# AlarmClock.net
KiCad netlist of a schematic drawn in EAGLE
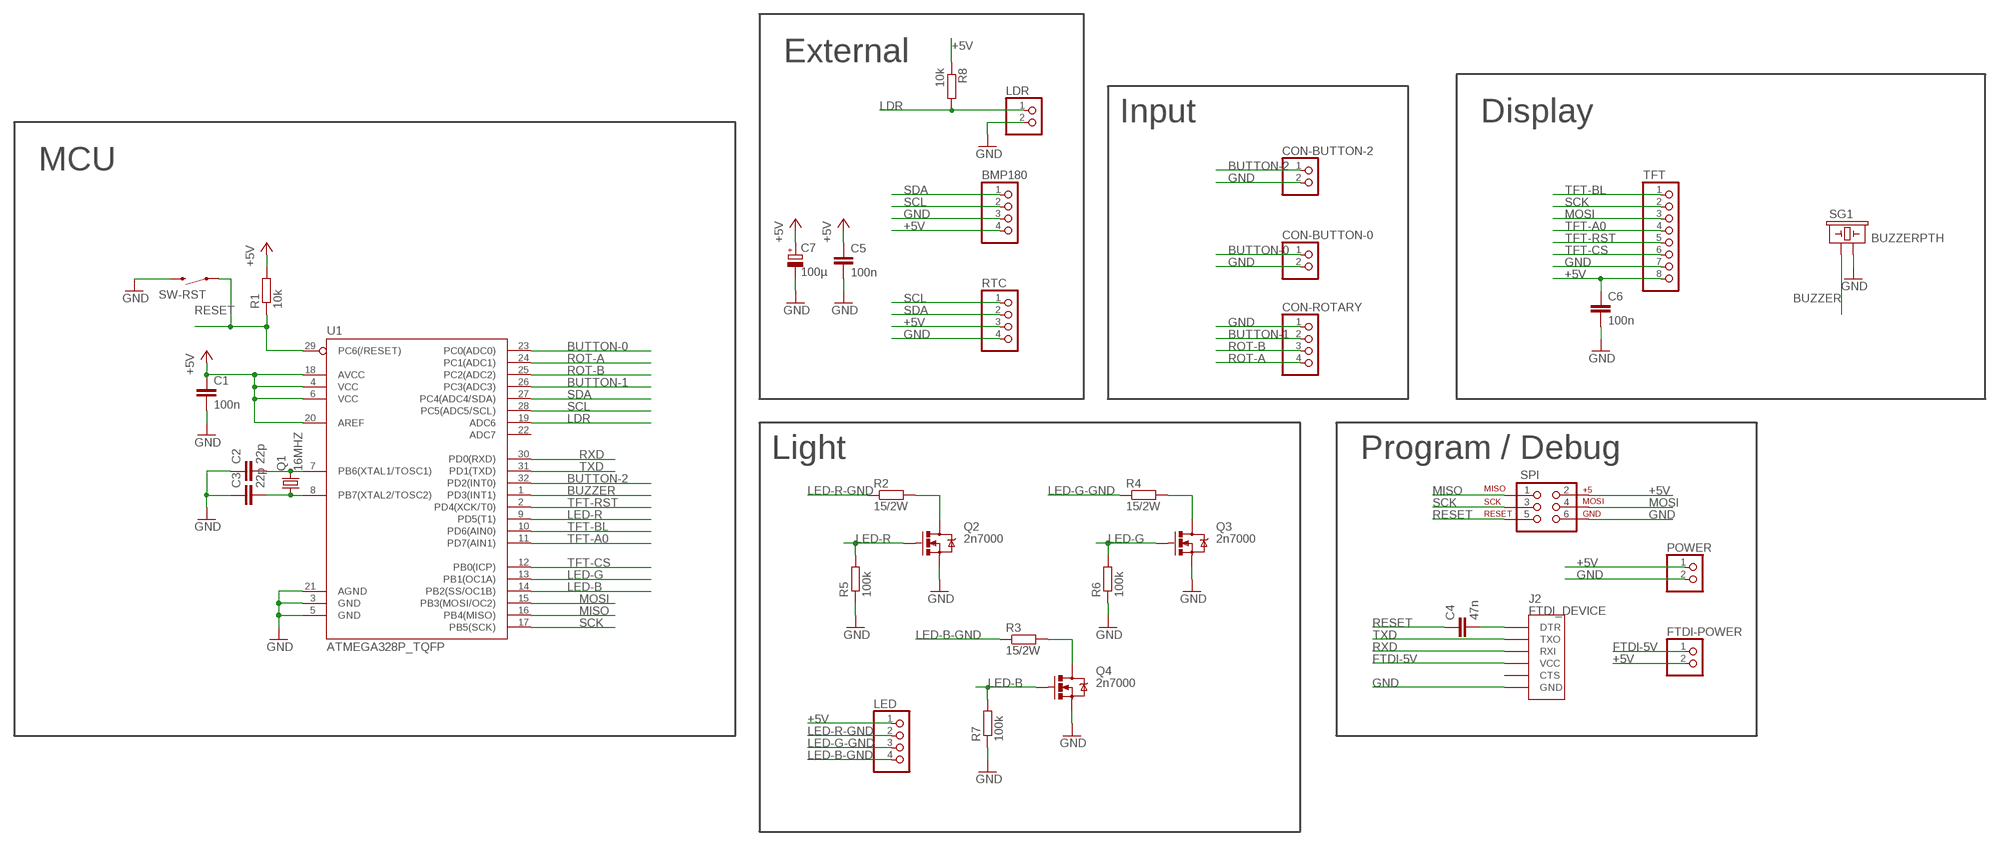
[diagram p0: schematic, sheet 1]

(export (version "E")
  (design (tool "Eeschema 10.0.6"))
  (components
    (comp (ref "BMP180")
      (value "PINHD-1X4")
      (footprint "eagle-import:1X04")
      (libsource (lib "eagle-import") (part "PINHD-1X4"))
    )
    (comp (ref "C1")
      (value "100n")
      (footprint "eagle-import:C0805")
      (libsource (lib "eagle-import") (part "C-EUC0805"))
    )
    (comp (ref "C2")
      (value "22p")
      (footprint "eagle-import:C0805")
      (libsource (lib "eagle-import") (part "C-EUC0805"))
    )
    (comp (ref "C3")
      (value "22p")
      (footprint "eagle-import:C0805")
      (libsource (lib "eagle-import") (part "C-EUC0805"))
    )
    (comp (ref "C4")
      (value "47n")
      (footprint "eagle-import:C0805")
      (libsource (lib "eagle-import") (part "C-EUC0805"))
    )
    (comp (ref "C5")
      (value "100n")
      (footprint "eagle-import:C0805")
      (libsource (lib "eagle-import") (part "C-EUC0805"))
    )
    (comp (ref "C6")
      (value "100n")
      (footprint "eagle-import:C0805")
      (libsource (lib "eagle-import") (part "C-EUC0805"))
    )
    (comp (ref "C7")
      (value "100µ")
      (footprint "eagle-import:PANASONIC_F")
      (libsource (lib "eagle-import") (part "CPOL-EUF"))
    )
    (comp (ref "CON-BUTTON-0")
      (value "PINHD-1X2/90")
      (footprint "eagle-import:1X02_90")
      (libsource (lib "eagle-import") (part "PINHD-1X2/90"))
    )
    (comp (ref "CON-BUTTON-2")
      (value "PINHD-1X2/90")
      (footprint "eagle-import:1X02_90")
      (libsource (lib "eagle-import") (part "PINHD-1X2/90"))
    )
    (comp (ref "CON-ROTARY")
      (value "PINHD-1X4/90")
      (footprint "eagle-import:1X04_90")
      (libsource (lib "eagle-import") (part "PINHD-1X4/90"))
    )
    (comp (ref "FTDI-POWER")
      (value "PINHD-1X2")
      (footprint "eagle-import:1X02")
      (libsource (lib "eagle-import") (part "PINHD-1X2"))
    )
    (comp (ref "J2")
      (value "FTDI_DEVICE")
      (footprint "eagle-import:FTDI_DEVICE_SIDE")
      (libsource (lib "eagle-import") (part "FTDI_DEVICE"))
    )
    (comp (ref "LDR")
      (value "PINHD-1X2")
      (footprint "eagle-import:1X02")
      (libsource (lib "eagle-import") (part "PINHD-1X2"))
    )
    (comp (ref "LED")
      (value "PINHD-1X4")
      (footprint "eagle-import:1X04")
      (libsource (lib "eagle-import") (part "PINHD-1X4"))
    )
    (comp (ref "POWER")
      (value "PINHD-1X2")
      (footprint "eagle-import:1X02")
      (libsource (lib "eagle-import") (part "PINHD-1X2"))
    )
    (comp (ref "Q1")
      (value "16MHZ")
      (footprint "eagle-import:HC49UP")
      (libsource (lib "eagle-import") (part "CRYSTALHC49UP"))
    )
    (comp (ref "Q2")
      (value "2n7000")
      (footprint "eagle-import:TO-92")
      (libsource (lib "eagle-import") (part "MOSFET-NCHANNEL2N7000"))
    )
    (comp (ref "Q3")
      (value "2n7000")
      (footprint "eagle-import:TO-92")
      (libsource (lib "eagle-import") (part "MOSFET-NCHANNEL2N7000"))
    )
    (comp (ref "Q4")
      (value "2n7000")
      (footprint "eagle-import:TO-92")
      (libsource (lib "eagle-import") (part "MOSFET-NCHANNEL2N7000"))
    )
    (comp (ref "R1")
      (value "10k")
      (footprint "eagle-import:M0805")
      (libsource (lib "eagle-import") (part "R-EU_M0805"))
    )
    (comp (ref "R2")
      (value "15/2W")
      (footprint "eagle-import:0414_15")
      (libsource (lib "eagle-import") (part "R-EU_0414/15"))
    )
    (comp (ref "R3")
      (value "15/2W")
      (footprint "eagle-import:0414_15")
      (libsource (lib "eagle-import") (part "R-EU_0414/15"))
    )
    (comp (ref "R4")
      (value "15/2W")
      (footprint "eagle-import:0414_15")
      (libsource (lib "eagle-import") (part "R-EU_0414/15"))
    )
    (comp (ref "R5")
      (value "100k")
      (footprint "eagle-import:M0805")
      (libsource (lib "eagle-import") (part "R-EU_M0805"))
    )
    (comp (ref "R6")
      (value "100k")
      (footprint "eagle-import:M0805")
      (libsource (lib "eagle-import") (part "R-EU_M0805"))
    )
    (comp (ref "R7")
      (value "100k")
      (footprint "eagle-import:M0805")
      (libsource (lib "eagle-import") (part "R-EU_M0805"))
    )
    (comp (ref "R8")
      (value "10k")
      (footprint "eagle-import:R0805")
      (libsource (lib "eagle-import") (part "R-EU_R0805"))
    )
    (comp (ref "RTC")
      (value "PINHD-1X4")
      (footprint "eagle-import:1X04")
      (libsource (lib "eagle-import") (part "PINHD-1X4"))
    )
    (comp (ref "SG1")
      (value "BUZZERPTH")
      (footprint "eagle-import:BUZZER-12MM")
      (libsource (lib "eagle-import") (part "BUZZERPTH"))
    )
    (comp (ref "SPI")
      (value "AVR_SPI_PRG_6NS")
      (footprint "eagle-import:2X3-NS")
      (libsource (lib "eagle-import") (part "AVR_SPI_PRG_6NS"))
    )
    (comp (ref "SW-RST")
      (value "SWITCH-MOMENTARY-2SMD-1101NE")
      (footprint "eagle-import:TACTILE-SWITCH-1101NE")
      (libsource (lib "eagle-import") (part "SWITCH-MOMENTARY-2SMD-1101NE"))
    )
    (comp (ref "TFT")
      (value "PINHD-1X8")
      (footprint "eagle-import:1X08")
      (libsource (lib "eagle-import") (part "PINHD-1X8"))
    )
    (comp (ref "U1")
      (value "ATMEGA328P_TQFP")
      (footprint "eagle-import:TQFP32-08")
      (libsource (lib "eagle-import") (part "ATMEGA328P_TQFP"))
    )
  )
  (nets
    (net (code "1") (name "+5V") (class "Default")
      (node (ref "BMP180") (pin "4") (pinfunction "4_4") (pintype "passive"))
      (node (ref "C1") (pin "1") (pinfunction "1_1") (pintype "passive"))
      (node (ref "C5") (pin "1") (pinfunction "1_1") (pintype "passive"))
      (node (ref "C6") (pin "1") (pinfunction "1_1") (pintype "passive"))
      (node (ref "C7") (pin "+") (pinfunction "+_+") (pintype "passive"))
      (node (ref "FTDI-POWER") (pin "2") (pinfunction "2_2") (pintype "passive"))
      (node (ref "LED") (pin "1") (pinfunction "1_1") (pintype "passive"))
      (node (ref "POWER") (pin "1") (pinfunction "1_1") (pintype "passive"))
      (node (ref "R1") (pin "2") (pinfunction "2_2") (pintype "passive"))
      (node (ref "R8") (pin "1") (pinfunction "1_1") (pintype "passive"))
      (node (ref "RTC") (pin "3") (pinfunction "3_3") (pintype "passive"))
      (node (ref "SPI") (pin "2") (pinfunction "2_2") (pintype "passive"))
      (node (ref "TFT") (pin "8") (pinfunction "8_8") (pintype "passive"))
      (node (ref "U1") (pin "18") (pinfunction "AVCC_18") (pintype "bidirectional"))
      (node (ref "U1") (pin "20") (pinfunction "AREF_20") (pintype "bidirectional"))
      (node (ref "U1") (pin "4") (pinfunction "VCC_4") (pintype "bidirectional"))
      (node (ref "U1") (pin "6") (pinfunction "VCC_6") (pintype "bidirectional"))
    )
    (net (code "2") (name "/BUTTON-0") (class "Default")
      (node (ref "CON-BUTTON-0") (pin "1") (pinfunction "1_1") (pintype "passive"))
      (node (ref "U1") (pin "23") (pinfunction "PC0(ADC0)_23") (pintype "bidirectional"))
    )
    (net (code "3") (name "/BUTTON-1") (class "Default")
      (node (ref "CON-ROTARY") (pin "2") (pinfunction "2_2") (pintype "passive"))
      (node (ref "U1") (pin "26") (pinfunction "PC3(ADC3)_26") (pintype "bidirectional"))
    )
    (net (code "4") (name "/BUTTON-2") (class "Default")
      (node (ref "CON-BUTTON-2") (pin "1") (pinfunction "1_1") (pintype "passive"))
      (node (ref "U1") (pin "32") (pinfunction "PD2(INT0)_32") (pintype "bidirectional"))
    )
    (net (code "5") (name "/BUZZER") (class "Default")
      (node (ref "SG1") (pin "+") (pinfunction "1_+") (pintype "passive"))
      (node (ref "U1") (pin "1") (pinfunction "PD3(INT1)_1") (pintype "bidirectional"))
    )
    (net (code "6") (name "/FTDI-5V") (class "Default")
      (node (ref "FTDI-POWER") (pin "1") (pinfunction "1_1") (pintype "passive"))
      (node (ref "J2") (pin "P$4") (pinfunction "VCC_P$4") (pintype "bidirectional"))
    )
    (net (code "7") (name "/LDR") (class "Default")
      (node (ref "LDR") (pin "1") (pinfunction "1_1") (pintype "passive"))
      (node (ref "R8") (pin "2") (pinfunction "2_2") (pintype "passive"))
      (node (ref "U1") (pin "19") (pinfunction "ADC6_19") (pintype "bidirectional"))
    )
    (net (code "8") (name "/LED-B") (class "Default")
      (node (ref "Q4") (pin "2") (pinfunction "G_2") (pintype "passive"))
      (node (ref "R7") (pin "2") (pinfunction "2_2") (pintype "passive"))
      (node (ref "U1") (pin "14") (pinfunction "PB2(SS/OC1B)_14") (pintype "bidirectional"))
    )
    (net (code "9") (name "/LED-B-GND") (class "Default")
      (node (ref "LED") (pin "4") (pinfunction "4_4") (pintype "passive"))
      (node (ref "R3") (pin "1") (pinfunction "1_1") (pintype "passive"))
    )
    (net (code "10") (name "/LED-G") (class "Default")
      (node (ref "Q3") (pin "2") (pinfunction "G_2") (pintype "passive"))
      (node (ref "R6") (pin "2") (pinfunction "2_2") (pintype "passive"))
      (node (ref "U1") (pin "13") (pinfunction "PB1(OC1A)_13") (pintype "bidirectional"))
    )
    (net (code "11") (name "/LED-G-GND") (class "Default")
      (node (ref "LED") (pin "3") (pinfunction "3_3") (pintype "passive"))
      (node (ref "R4") (pin "1") (pinfunction "1_1") (pintype "passive"))
    )
    (net (code "12") (name "/LED-R") (class "Default")
      (node (ref "Q2") (pin "2") (pinfunction "G_2") (pintype "passive"))
      (node (ref "R5") (pin "2") (pinfunction "2_2") (pintype "passive"))
      (node (ref "U1") (pin "9") (pinfunction "PD5(T1)_9") (pintype "bidirectional"))
    )
    (net (code "13") (name "/LED-R-GND") (class "Default")
      (node (ref "LED") (pin "2") (pinfunction "2_2") (pintype "passive"))
      (node (ref "R2") (pin "1") (pinfunction "1_1") (pintype "passive"))
    )
    (net (code "14") (name "/MISO") (class "Default")
      (node (ref "SPI") (pin "1") (pinfunction "1_1") (pintype "passive"))
      (node (ref "U1") (pin "16") (pinfunction "PB4(MISO)_16") (pintype "bidirectional"))
    )
    (net (code "15") (name "/MOSI") (class "Default")
      (node (ref "SPI") (pin "4") (pinfunction "4_4") (pintype "passive"))
      (node (ref "TFT") (pin "3") (pinfunction "3_3") (pintype "passive"))
      (node (ref "U1") (pin "15") (pinfunction "PB3(MOSI/OC2)_15") (pintype "bidirectional"))
    )
    (net (code "16") (name "/RESET") (class "Default")
      (node (ref "C4") (pin "1") (pinfunction "1_1") (pintype "passive"))
      (node (ref "R1") (pin "1") (pinfunction "1_1") (pintype "passive"))
      (node (ref "SPI") (pin "5") (pinfunction "5_5") (pintype "passive"))
      (node (ref "SW-RST") (pin "1") (pinfunction "1_1") (pintype "passive"))
      (node (ref "U1") (pin "29") (pinfunction "PC6(/RESET)_29") (pintype "bidirectional"))
    )
    (net (code "17") (name "/ROT-A") (class "Default")
      (node (ref "CON-ROTARY") (pin "4") (pinfunction "4_4") (pintype "passive"))
      (node (ref "U1") (pin "24") (pinfunction "PC1(ADC1)_24") (pintype "bidirectional"))
    )
    (net (code "18") (name "/ROT-B") (class "Default")
      (node (ref "CON-ROTARY") (pin "3") (pinfunction "3_3") (pintype "passive"))
      (node (ref "U1") (pin "25") (pinfunction "PC2(ADC2)_25") (pintype "bidirectional"))
    )
    (net (code "19") (name "/RXD") (class "Default")
      (node (ref "J2") (pin "P$3") (pinfunction "RXI_P$3") (pintype "bidirectional"))
      (node (ref "U1") (pin "30") (pinfunction "PD0(RXD)_30") (pintype "bidirectional"))
    )
    (net (code "20") (name "/SCK") (class "Default")
      (node (ref "SPI") (pin "3") (pinfunction "3_3") (pintype "passive"))
      (node (ref "TFT") (pin "2") (pinfunction "2_2") (pintype "passive"))
      (node (ref "U1") (pin "17") (pinfunction "PB5(SCK)_17") (pintype "bidirectional"))
    )
    (net (code "21") (name "/SCL") (class "Default")
      (node (ref "BMP180") (pin "2") (pinfunction "2_2") (pintype "passive"))
      (node (ref "RTC") (pin "1") (pinfunction "1_1") (pintype "passive"))
      (node (ref "U1") (pin "28") (pinfunction "PC5(ADC5/SCL)_28") (pintype "bidirectional"))
    )
    (net (code "22") (name "/SDA") (class "Default")
      (node (ref "BMP180") (pin "1") (pinfunction "1_1") (pintype "passive"))
      (node (ref "RTC") (pin "2") (pinfunction "2_2") (pintype "passive"))
      (node (ref "U1") (pin "27") (pinfunction "PC4(ADC4/SDA)_27") (pintype "bidirectional"))
    )
    (net (code "23") (name "/TFT-A0") (class "Default")
      (node (ref "TFT") (pin "4") (pinfunction "4_4") (pintype "passive"))
      (node (ref "U1") (pin "11") (pinfunction "PD7(AIN1)_11") (pintype "bidirectional"))
    )
    (net (code "24") (name "/TFT-BL") (class "Default")
      (node (ref "TFT") (pin "1") (pinfunction "1_1") (pintype "passive"))
      (node (ref "U1") (pin "10") (pinfunction "PD6(AIN0)_10") (pintype "bidirectional"))
    )
    (net (code "25") (name "/TFT-CS") (class "Default")
      (node (ref "TFT") (pin "6") (pinfunction "6_6") (pintype "passive"))
      (node (ref "U1") (pin "12") (pinfunction "PB0(ICP)_12") (pintype "bidirectional"))
    )
    (net (code "26") (name "/TFT-RST") (class "Default")
      (node (ref "TFT") (pin "5") (pinfunction "5_5") (pintype "passive"))
      (node (ref "U1") (pin "2") (pinfunction "PD4(XCK/T0)_2") (pintype "bidirectional"))
    )
    (net (code "27") (name "/TXD") (class "Default")
      (node (ref "J2") (pin "P$2") (pinfunction "TXO_P$2") (pintype "bidirectional"))
      (node (ref "U1") (pin "31") (pinfunction "PD1(TXD)_31") (pintype "bidirectional"))
    )
    (net (code "28") (name "GND") (class "Default")
      (node (ref "BMP180") (pin "3") (pinfunction "3_3") (pintype "passive"))
      (node (ref "C1") (pin "2") (pinfunction "2_2") (pintype "passive"))
      (node (ref "C2") (pin "1") (pinfunction "1_1") (pintype "passive"))
      (node (ref "C3") (pin "1") (pinfunction "1_1") (pintype "passive"))
      (node (ref "C5") (pin "2") (pinfunction "2_2") (pintype "passive"))
      (node (ref "C6") (pin "2") (pinfunction "2_2") (pintype "passive"))
      (node (ref "C7") (pin "-") (pinfunction "-_-") (pintype "passive"))
      (node (ref "CON-BUTTON-0") (pin "2") (pinfunction "2_2") (pintype "passive"))
      (node (ref "CON-BUTTON-2") (pin "2") (pinfunction "2_2") (pintype "passive"))
      (node (ref "CON-ROTARY") (pin "1") (pinfunction "1_1") (pintype "passive"))
      (node (ref "J2") (pin "P$6") (pinfunction "GND_P$6") (pintype "bidirectional"))
      (node (ref "LDR") (pin "2") (pinfunction "2_2") (pintype "passive"))
      (node (ref "POWER") (pin "2") (pinfunction "2_2") (pintype "passive"))
      (node (ref "Q2") (pin "1") (pinfunction "S_1") (pintype "passive"))
      (node (ref "Q3") (pin "1") (pinfunction "S_1") (pintype "passive"))
      (node (ref "Q4") (pin "1") (pinfunction "S_1") (pintype "passive"))
      (node (ref "R5") (pin "1") (pinfunction "1_1") (pintype "passive"))
      (node (ref "R6") (pin "1") (pinfunction "1_1") (pintype "passive"))
      (node (ref "R7") (pin "1") (pinfunction "1_1") (pintype "passive"))
      (node (ref "RTC") (pin "4") (pinfunction "4_4") (pintype "passive"))
      (node (ref "SG1") (pin "-") (pinfunction "2_-") (pintype "passive"))
      (node (ref "SPI") (pin "6") (pinfunction "6_6") (pintype "passive"))
      (node (ref "SW-RST") (pin "2") (pinfunction "2_2") (pintype "passive"))
      (node (ref "TFT") (pin "7") (pinfunction "7_7") (pintype "passive"))
      (node (ref "U1") (pin "21") (pinfunction "AGND_21") (pintype "bidirectional"))
      (node (ref "U1") (pin "3") (pinfunction "GND_3") (pintype "bidirectional"))
      (node (ref "U1") (pin "5") (pinfunction "GND_5") (pintype "bidirectional"))
    )
    (net (code "29") (name "Net-(J2-DTR)") (class "Default")
      (node (ref "C4") (pin "2") (pinfunction "2_2") (pintype "passive"))
      (node (ref "J2") (pin "P$1") (pinfunction "DTR_P$1") (pintype "bidirectional"))
    )
    (net (code "30") (name "Net-(Q2-D)") (class "Default")
      (node (ref "Q2") (pin "3") (pinfunction "D_3") (pintype "passive"))
      (node (ref "R2") (pin "2") (pinfunction "2_2") (pintype "passive"))
    )
    (net (code "31") (name "Net-(Q3-D)") (class "Default")
      (node (ref "Q3") (pin "3") (pinfunction "D_3") (pintype "passive"))
      (node (ref "R4") (pin "2") (pinfunction "2_2") (pintype "passive"))
    )
    (net (code "32") (name "Net-(Q4-D)") (class "Default")
      (node (ref "Q4") (pin "3") (pinfunction "D_3") (pintype "passive"))
      (node (ref "R3") (pin "2") (pinfunction "2_2") (pintype "passive"))
    )
    (net (code "33") (name "Net-(U1-PB6(XTAL1{slash}TOSC1))") (class "Default")
      (node (ref "C2") (pin "2") (pinfunction "2_2") (pintype "passive"))
      (node (ref "Q1") (pin "2") (pinfunction "2_2") (pintype "passive"))
      (node (ref "U1") (pin "7") (pinfunction "PB6(XTAL1/TOSC1)_7") (pintype "bidirectional"))
    )
    (net (code "34") (name "Net-(U1-PB7(XTAL2{slash}TOSC2))") (class "Default")
      (node (ref "C3") (pin "2") (pinfunction "2_2") (pintype "passive"))
      (node (ref "Q1") (pin "1") (pinfunction "1_1") (pintype "passive"))
      (node (ref "U1") (pin "8") (pinfunction "PB7(XTAL2/TOSC2)_8") (pintype "bidirectional"))
    )
    (net (code "35") (name "unconnected-(J2-CTS-PadP$5)") (class "Default")
      (node (ref "J2") (pin "P$5") (pinfunction "CTS_P$5") (pintype "bidirectional"))
    )
    (net (code "36") (name "unconnected-(U1-ADC7-Pad22)") (class "Default")
      (node (ref "U1") (pin "22") (pinfunction "ADC7_22") (pintype "bidirectional"))
    )
  )
)
